# Safety_Loops.net
KiCad netlist of a schematic drawn in Altium Designer
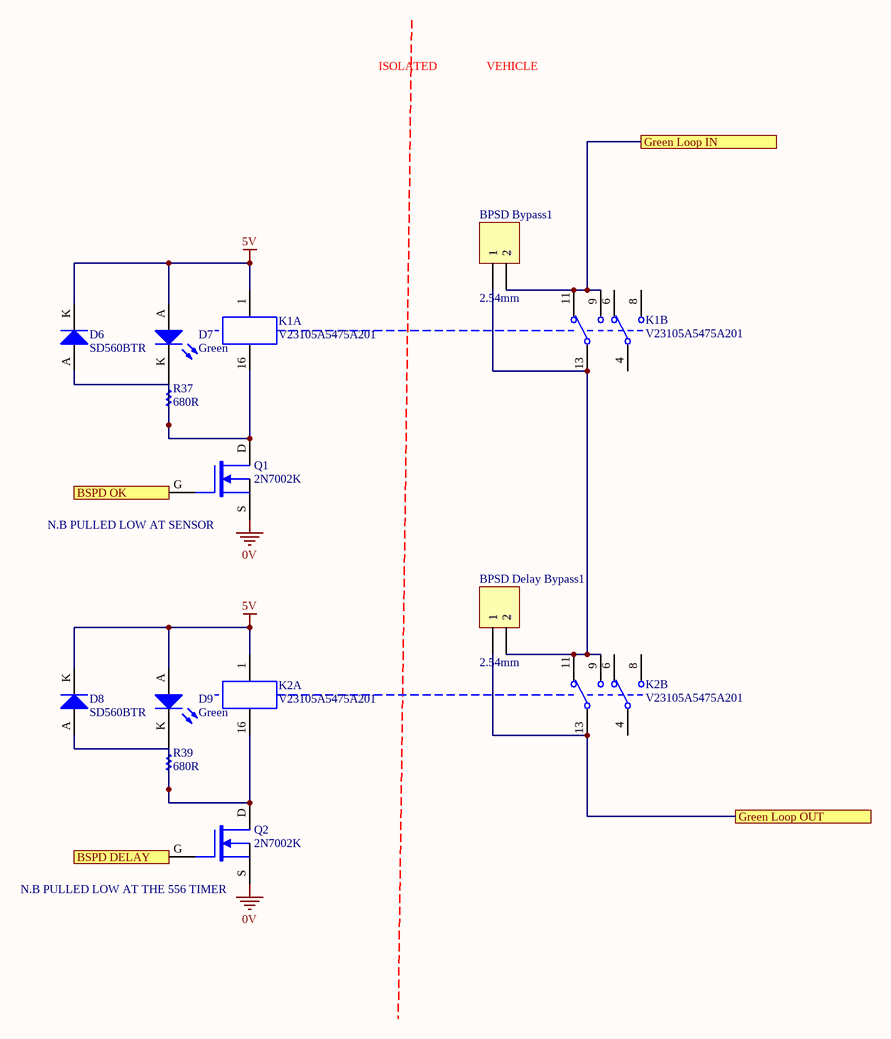
[diagram p0: Safety Loops.SchDoc]

(export (version "E")
  (design (tool "Eeschema 10.0.6"))
  (components
    (comp (ref "BPSD Bypass1")
      (value "2.54mm")
      (footprint "TH 2.54mm Header 1x2")
      (fields (field (name "PART NUMBER") "TH 2.54mm Header 1x2") (field (name "CONTACT") "NA"))
      (libsource (lib "ts_20-standard-connectors") (part "Header 1x2"))
    )
    (comp (ref "BPSD Delay Bypass1")
      (value "2.54mm")
      (footprint "TH 2.54mm Header 1x2")
      (fields (field (name "PART NUMBER") "TH 2.54mm Header 1x2") (field (name "CONTACT") "NA"))
      (libsource (lib "ts_20-standard-connectors") (part "Header 1x2"))
    )
    (comp (ref "D6")
      (value "SD560BTR")
      (footprint "SMB Diode")
      (description "1.2V_F 600V 5A SMB")
      (fields
        (field (name "MANUFACTURER") "SMC Diode Solutions")
        (field (name "DIGIKEY PART NUMBER") "1655-1530-2-ND")
      )
      (libsource (lib "ts_20-standard-library") (part "Diode"))
    )
    (comp (ref "D7")
      (value "Green")
      (footprint "0805 LED")
      (description "Green LED Indication - Discrete 1.75V 0805 (2012 Metric)")
      (fields (field (name "PART NUMBER") "SML-210FTT86") (field (name "MANUFACTURER") "ROHM Semiconductor"))
      (libsource (lib "ts_20-standard-library") (part "LED"))
    )
    (comp (ref "D8")
      (value "SD560BTR")
      (footprint "SMB Diode")
      (description "1.2V_F 600V 5A SMB")
      (fields
        (field (name "MANUFACTURER") "SMC Diode Solutions")
        (field (name "DIGIKEY PART NUMBER") "1655-1530-2-ND")
      )
      (libsource (lib "ts_20-standard-library") (part "Diode"))
    )
    (comp (ref "D9")
      (value "Green")
      (footprint "0805 LED")
      (description "Green LED Indication - Discrete 1.75V 0805 (2012 Metric)")
      (fields (field (name "PART NUMBER") "SML-210FTT86") (field (name "MANUFACTURER") "ROHM Semiconductor"))
      (libsource (lib "ts_20-standard-library") (part "LED"))
    )
    (comp (ref "K1")
      (value "V23105A5475A201")
      (footprint "TI 2-DIL")
      (description "5V DPDT Relay 3A 220VDC")
      (fields (field (name "MANUFACTURER") "Axicom") (field (name "DIGIKEY PART NUMBER") "PB383-ND"))
      (libsource (lib "ts_20-standard-library") (part "V23105A5475A201"))
    )
    (comp (ref "K2")
      (value "V23105A5475A201")
      (footprint "TI 2-DIL")
      (description "5V DPDT Relay 3A 220VDC")
      (fields (field (name "MANUFACTURER") "Axicom") (field (name "DIGIKEY PART NUMBER") "PB383-ND"))
      (libsource (lib "") (part "V23105A5475A201_1"))
    )
    (comp (ref "Q1")
      (value "2N7002K")
      (footprint "ON SOT-23 MOSFET")
      (description "60V 380mA, NFET MOSTFET (Small Signal)")
      (fields
        (field (name "MANUFACTURER") "ON Semiconductor")
        (field (name "DIGIKEY PART NUMBER") "2N7002KCT-ND")
        (field (name "PUBLISHER") "Altium Limited")
      )
      (libsource (lib "ts_20-standard-library") (part "MOSFET-N"))
    )
    (comp (ref "Q2")
      (value "2N7002K")
      (footprint "ON SOT-23 MOSFET")
      (description "60V 380mA, NFET MOSTFET (Small Signal)")
      (fields
        (field (name "MANUFACTURER") "ON Semiconductor")
        (field (name "DIGIKEY PART NUMBER") "2N7002KCT-ND")
        (field (name "PUBLISHER") "Altium Limited")
      )
      (libsource (lib "ts_20-standard-library") (part "MOSFET-N"))
    )
    (comp (ref "R37")
      (value "680R")
      (footprint "0805")
      (fields
        (field (name "PART NUMBER") "RC0805FR07680RL")
        (field (name "MANUFACTURER") "YAGEO")
        (field (name "TOLERANCE") "0.01")
      )
      (libsource (lib "ts_20-standard-library") (part "Resistor"))
    )
    (comp (ref "R39")
      (value "680R")
      (footprint "0805")
      (fields
        (field (name "PART NUMBER") "RC0805FR07680RL")
        (field (name "MANUFACTURER") "YAGEO")
        (field (name "TOLERANCE") "0.01")
      )
      (libsource (lib "ts_20-standard-library") (part "Resistor"))
    )
  )
  (nets
    (net (code "1") (name "/BSPD DELAY") (class "Default")
      (node (ref "Q2") (pin "G") (pinfunction "G_G") (pintype "passive"))
    )
    (net (code "2") (name "/BSPD OK") (class "Default")
      (node (ref "Q1") (pin "G") (pinfunction "G_G") (pintype "passive"))
    )
    (net (code "3") (name "/Green Loop IN") (class "Default")
      (node (ref "BPSD Bypass1") (pin "2") (pinfunction "2_2") (pintype "passive"))
      (node (ref "K1") (pin "11") (pinfunction "11_11") (pintype "passive"))
      (node (ref "K1") (pin "9") (pinfunction "9_9") (pintype "passive"))
    )
    (net (code "4") (name "/Green Loop OUT") (class "Default")
      (node (ref "BPSD Delay Bypass1") (pin "1") (pinfunction "1_1") (pintype "passive"))
      (node (ref "K2") (pin "13") (pinfunction "13_13") (pintype "passive"))
    )
    (net (code "5") (name "0V") (class "Default")
      (node (ref "Q1") (pin "S") (pinfunction "S_S") (pintype "passive"))
      (node (ref "Q2") (pin "S") (pinfunction "S_S") (pintype "passive"))
    )
    (net (code "6") (name "5V") (class "Default")
      (node (ref "D6") (pin "K") (pinfunction "K_K") (pintype "passive"))
      (node (ref "D7") (pin "A") (pinfunction "A_A") (pintype "passive"))
      (node (ref "D8") (pin "K") (pinfunction "K_K") (pintype "passive"))
      (node (ref "D9") (pin "A") (pinfunction "A_A") (pintype "passive"))
      (node (ref "K1") (pin "1") (pinfunction "1_1") (pintype "passive"))
      (node (ref "K2") (pin "1") (pinfunction "1_1") (pintype "passive"))
    )
    (net (code "7") (name "Net-(BPSD Bypass1-Pad1)") (class "Default")
      (node (ref "BPSD Bypass1") (pin "1") (pinfunction "1_1") (pintype "passive"))
      (node (ref "BPSD Delay Bypass1") (pin "2") (pinfunction "2_2") (pintype "passive"))
      (node (ref "K1") (pin "13") (pinfunction "13_13") (pintype "passive"))
      (node (ref "K2") (pin "11") (pinfunction "11_11") (pintype "passive"))
      (node (ref "K2") (pin "9") (pinfunction "9_9") (pintype "passive"))
    )
    (net (code "8") (name "Net-(D6-PadA)") (class "Default")
      (node (ref "D6") (pin "A") (pinfunction "A_A") (pintype "passive"))
      (node (ref "K1") (pin "16") (pinfunction "16_16") (pintype "passive"))
      (node (ref "Q1") (pin "D") (pinfunction "D_D") (pintype "passive"))
      (node (ref "R37") (pin "1") (pinfunction "1_1") (pintype "passive"))
    )
    (net (code "9") (name "Net-(D7-PadK)") (class "Default")
      (node (ref "D7") (pin "K") (pinfunction "K_K") (pintype "passive"))
      (node (ref "R37") (pin "2") (pinfunction "2_2") (pintype "passive"))
    )
    (net (code "10") (name "Net-(D8-PadA)") (class "Default")
      (node (ref "D8") (pin "A") (pinfunction "A_A") (pintype "passive"))
      (node (ref "K2") (pin "16") (pinfunction "16_16") (pintype "passive"))
      (node (ref "Q2") (pin "D") (pinfunction "D_D") (pintype "passive"))
      (node (ref "R39") (pin "1") (pinfunction "1_1") (pintype "passive"))
    )
    (net (code "11") (name "Net-(D9-PadK)") (class "Default")
      (node (ref "D9") (pin "K") (pinfunction "K_K") (pintype "passive"))
      (node (ref "R39") (pin "2") (pinfunction "2_2") (pintype "passive"))
    )
    (net (code "12") (name "unconnected-(K1-Pad4)") (class "Default")
      (node (ref "K1") (pin "4") (pinfunction "4_4") (pintype "passive"))
    )
    (net (code "13") (name "unconnected-(K1-Pad6)") (class "Default")
      (node (ref "K1") (pin "6") (pinfunction "6_6") (pintype "passive"))
    )
    (net (code "14") (name "unconnected-(K1-Pad8)") (class "Default")
      (node (ref "K1") (pin "8") (pinfunction "8_8") (pintype "passive"))
    )
    (net (code "15") (name "unconnected-(K2-Pad4)") (class "Default")
      (node (ref "K2") (pin "4") (pinfunction "4_4") (pintype "passive"))
    )
    (net (code "16") (name "unconnected-(K2-Pad6)") (class "Default")
      (node (ref "K2") (pin "6") (pinfunction "6_6") (pintype "passive"))
    )
    (net (code "17") (name "unconnected-(K2-Pad8)") (class "Default")
      (node (ref "K2") (pin "8") (pinfunction "8_8") (pintype "passive"))
    )
  )
)
